# 11_-_POWER.net
KiCad netlist of a schematic drawn in Altium Designer
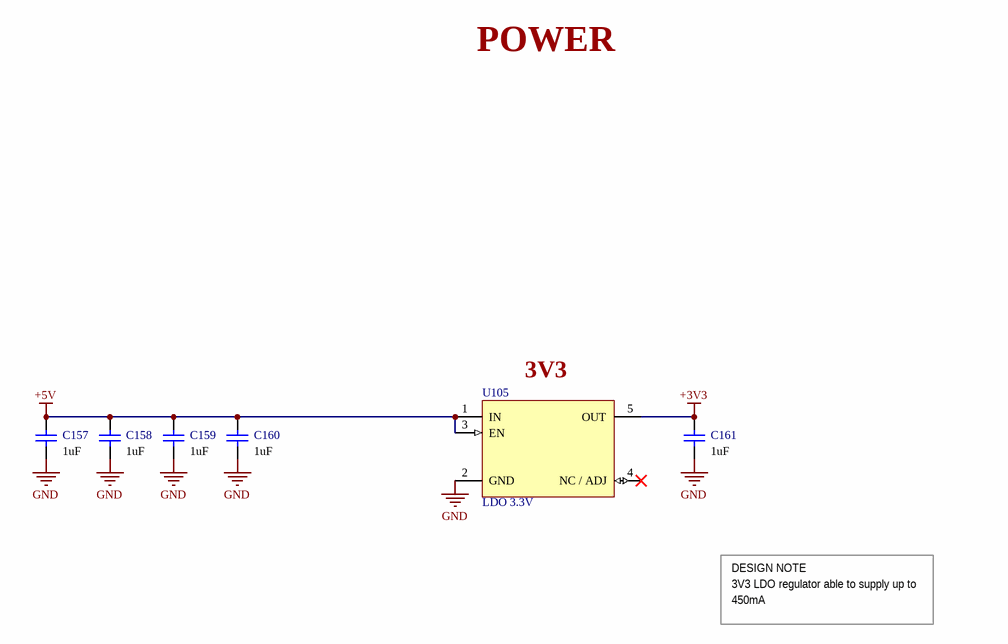
[diagram p0: [11] - POWER.SchDoc]

(export (version "E")
  (design (tool "Eeschema 10.0.6"))
  (components
    (comp (ref "C157")
      (value "1uF")
      (footprint "C0603")
      (description "C0603")
      (fields (field (name "Comment") "02016D104KAT2A"))
      (libsource (lib "Passive components") (part "02016D104KAT2A"))
    )
    (comp (ref "C158")
      (value "1uF")
      (footprint "C0603")
      (description "C0603")
      (fields (field (name "Comment") "02016D104KAT2A"))
      (libsource (lib "Passive components") (part "02016D104KAT2A"))
    )
    (comp (ref "C159")
      (value "1uF")
      (footprint "C0603")
      (description "C0603")
      (fields (field (name "Comment") "02016D104KAT2A"))
      (libsource (lib "Passive components") (part "02016D104KAT2A"))
    )
    (comp (ref "C160")
      (value "1uF")
      (footprint "C0603")
      (description "C0603")
      (fields (field (name "Comment") "02016D104KAT2A"))
      (libsource (lib "Passive components") (part "02016D104KAT2A"))
    )
    (comp (ref "C161")
      (value "1uF")
      (footprint "C0603")
      (description "C0603")
      (fields (field (name "Comment") "02016D104KAT2A"))
      (libsource (lib "Passive components") (part "02016D104KAT2A"))
    )
    (comp (ref "U105")
      (value "LDO 3.3V")
      (footprint "NCV8161BSN330T1G")
      (description "LDO fixed 3.3V 450mA ultra-low noise")
      (libsource (lib "Voltage regulators") (part "NCV8161BSN330T1G"))
    )
  )
  (nets
    (net (code "1") (name "+3V3") (class "Default")
      (node (ref "C161") (pin "2") (pinfunction "2_2") (pintype "passive"))
      (node (ref "U105") (pin "5") (pinfunction "OUT_5") (pintype "power_in"))
    )
    (net (code "2") (name "+5V") (class "Default")
      (node (ref "C157") (pin "2") (pinfunction "2_2") (pintype "passive"))
      (node (ref "C158") (pin "2") (pinfunction "2_2") (pintype "passive"))
      (node (ref "C159") (pin "2") (pinfunction "2_2") (pintype "passive"))
      (node (ref "C160") (pin "2") (pinfunction "2_2") (pintype "passive"))
      (node (ref "U105") (pin "1") (pinfunction "IN_1") (pintype "power_in"))
      (node (ref "U105") (pin "3") (pinfunction "EN_3") (pintype "input"))
    )
    (net (code "3") (name "GND") (class "Default")
      (node (ref "C157") (pin "1") (pinfunction "1_1") (pintype "passive"))
      (node (ref "C158") (pin "1") (pinfunction "1_1") (pintype "passive"))
      (node (ref "C159") (pin "1") (pinfunction "1_1") (pintype "passive"))
      (node (ref "C160") (pin "1") (pinfunction "1_1") (pintype "passive"))
      (node (ref "C161") (pin "1") (pinfunction "1_1") (pintype "passive"))
      (node (ref "U105") (pin "2") (pinfunction "GND_2") (pintype "power_in"))
    )
    (net (code "4") (name "unconnected-(U105-NC_{slash}_ADJ-Pad4)") (class "Default")
      (node (ref "U105") (pin "4") (pinfunction "NC_/_ADJ_4") (pintype "bidirectional+no_connect"))
    )
  )
)
